# io-board-a-2.net
KiCad netlist of a schematic drawn in EAGLE
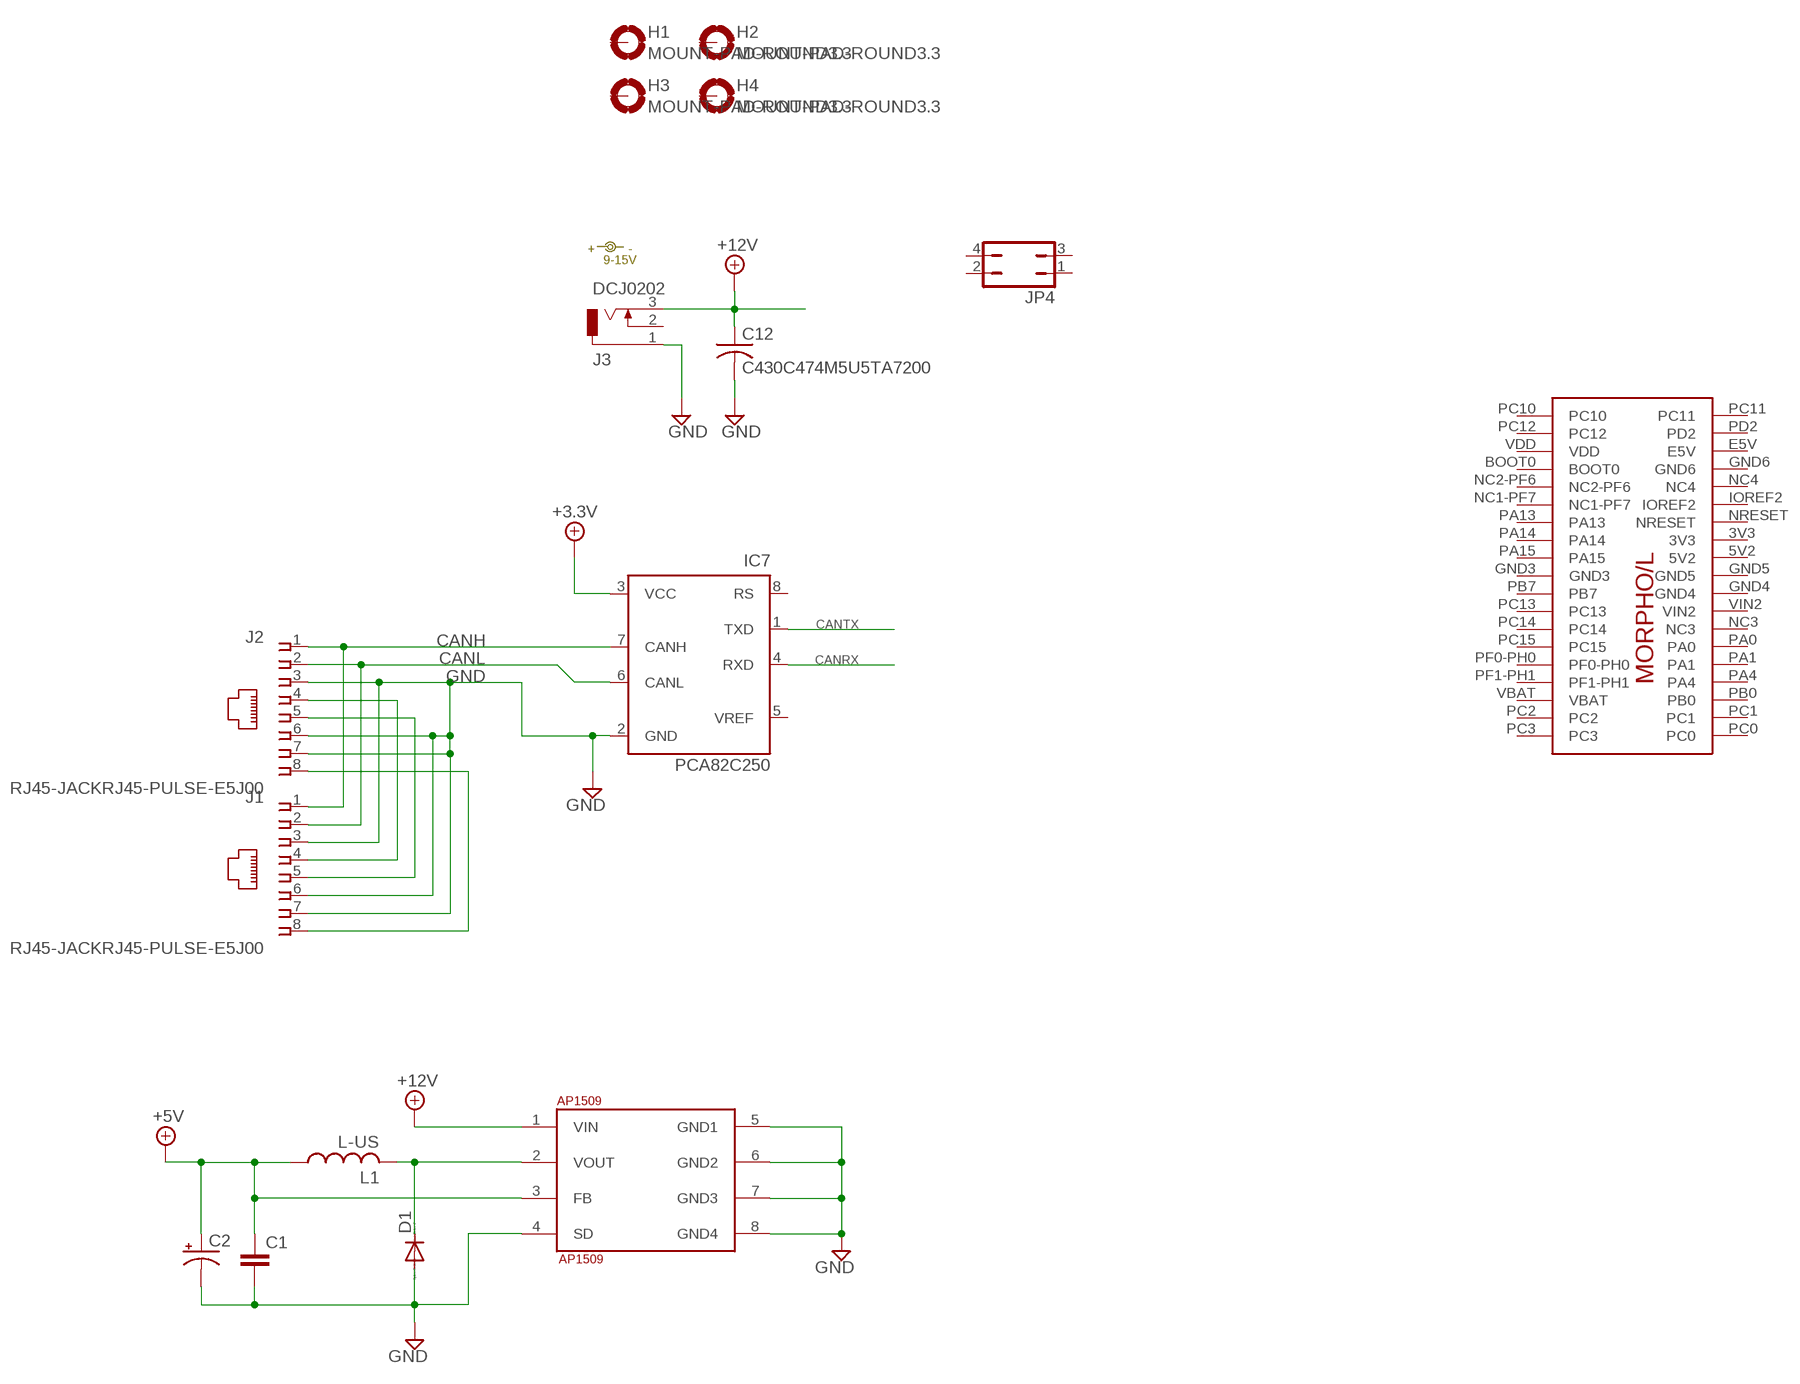
[diagram p0: schematic, sheet 1, part 1 of 2]
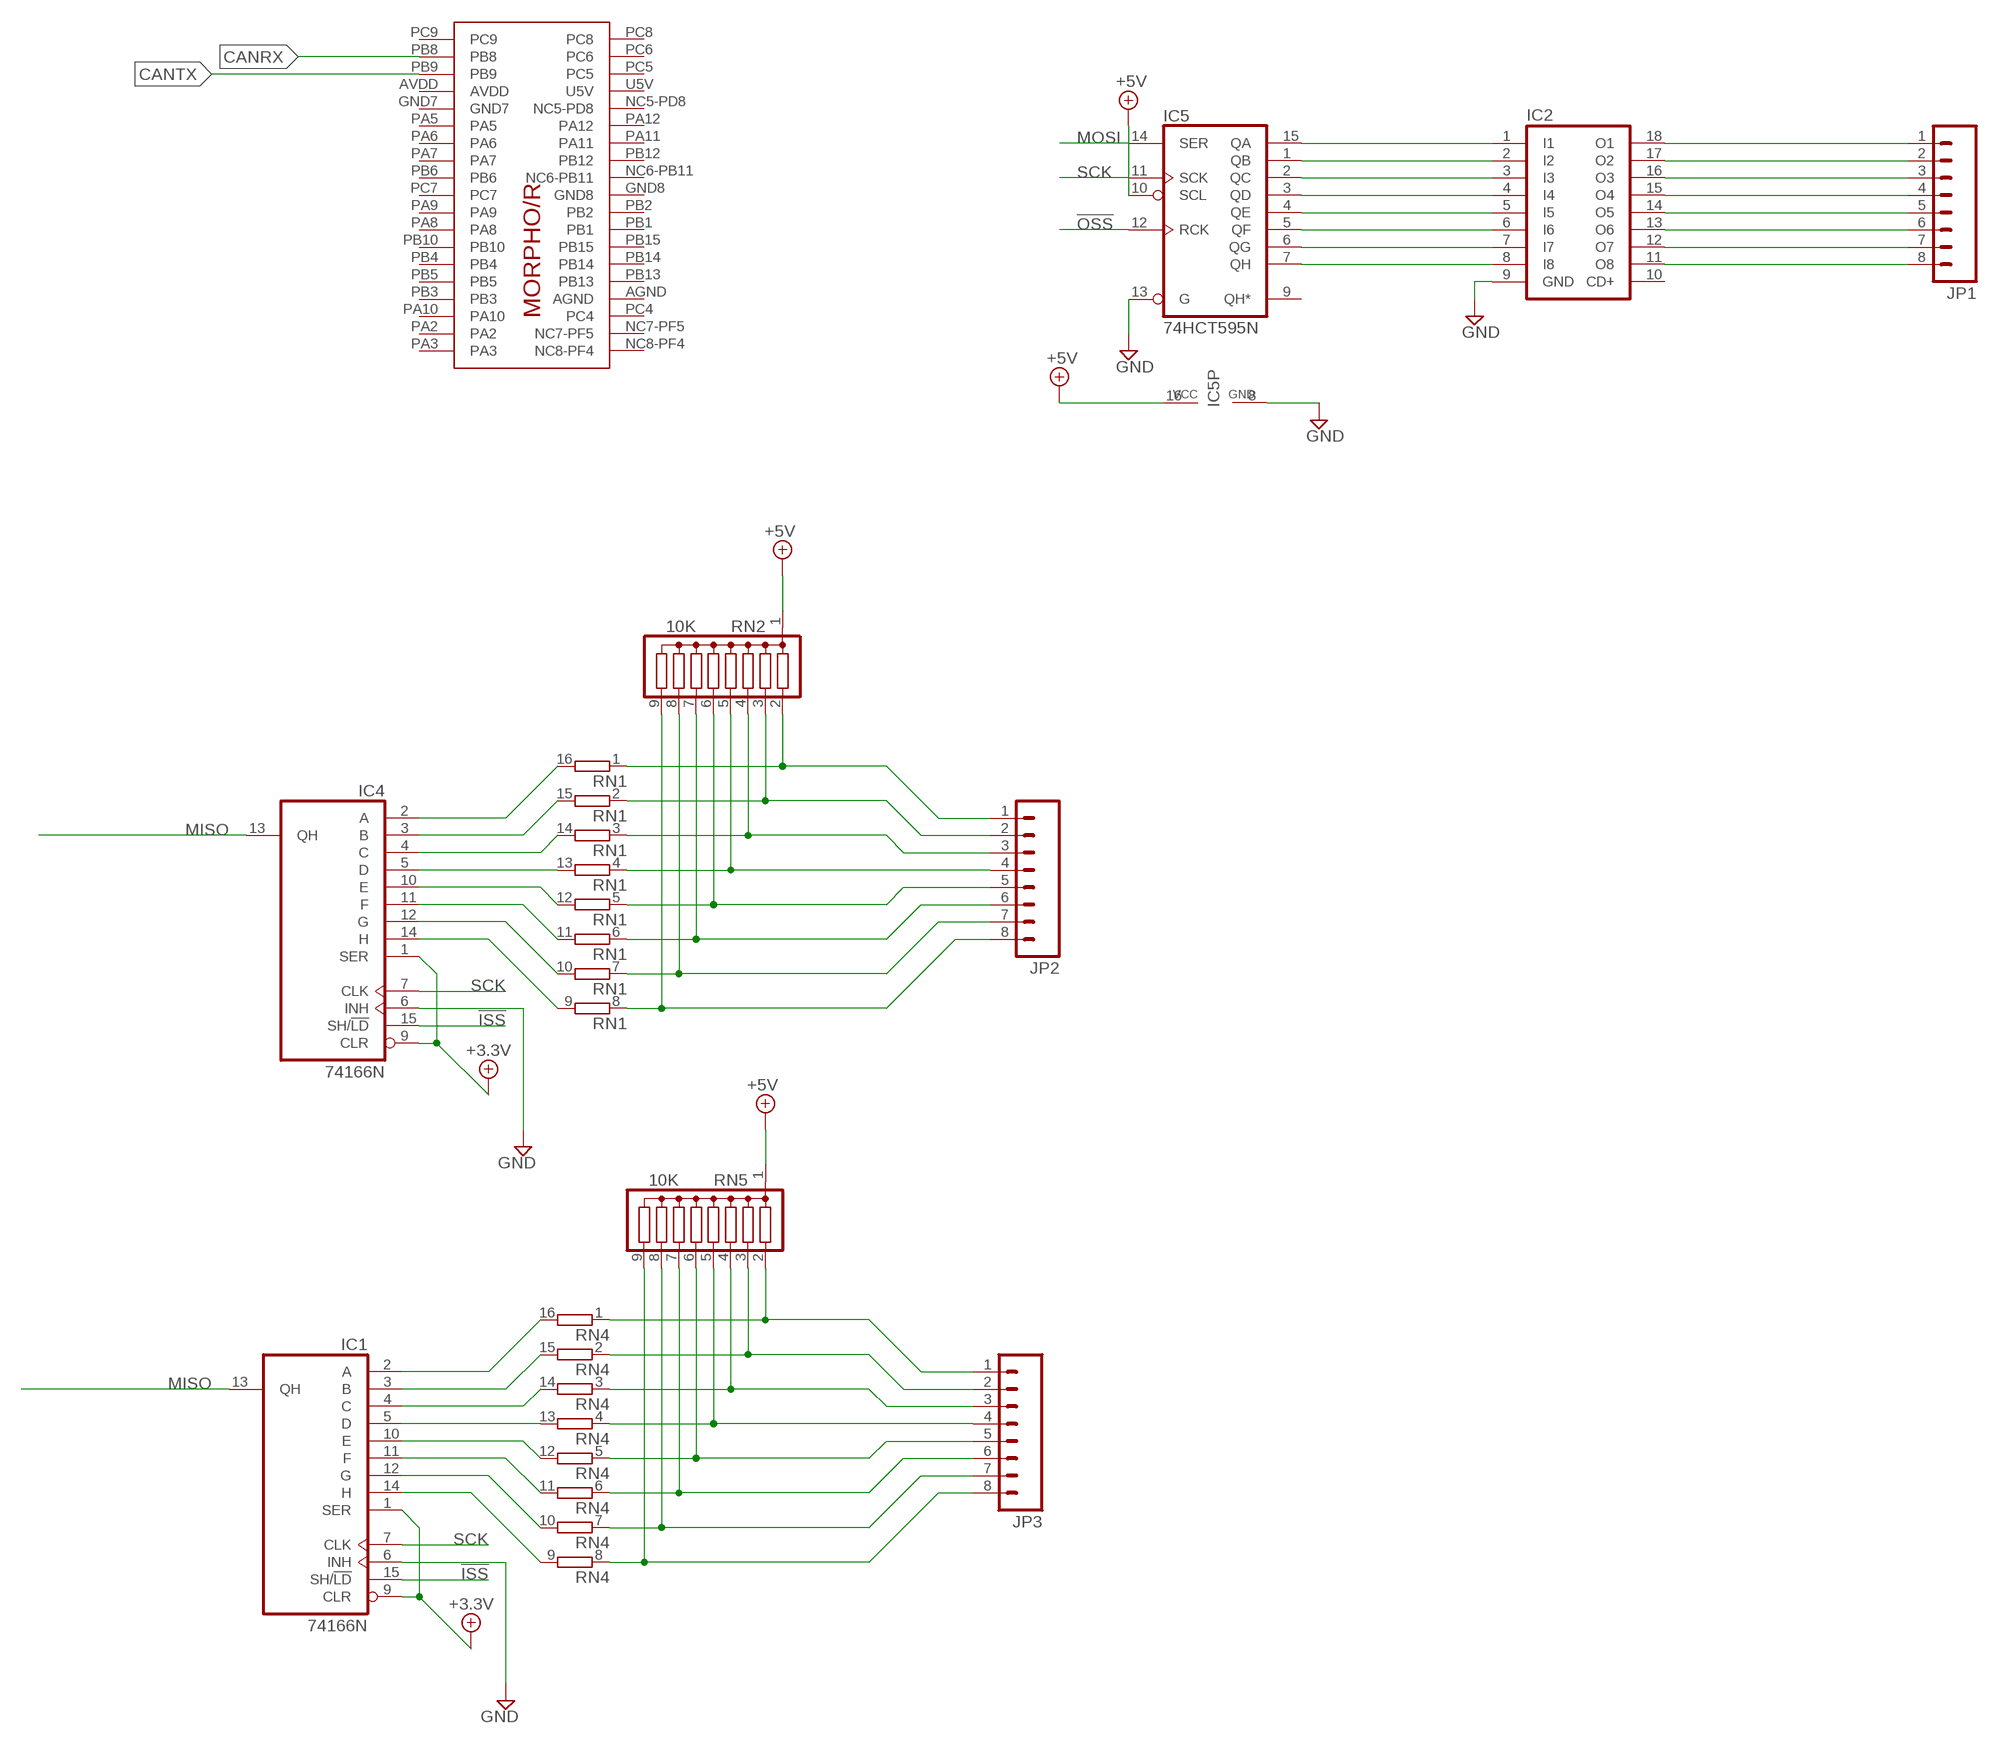
[diagram p1: schematic, sheet 1, part 2 of 2]

(export (version "E")
  (design (tool "Eeschema 10.0.6"))
  (components
    (comp (ref "+12V")
      (value "9-15V")
      (footprint "eagle-import:POWER_USAGE")
      (libsource (lib "eagle-import") (part "DOC-POWER_LABEL"))
    )
    (comp (ref "AP1509")
      (value "AP1509")
      (footprint "eagle-import:SO-08")
      (libsource (lib "eagle-import") (part "AP1509"))
    )
    (comp (ref "C1")
      (value "C-EUC1206")
      (footprint "eagle-import:C1206")
      (libsource (lib "eagle-import") (part "C-EUC1206"))
    )
    (comp (ref "C2")
      (value "CPOL-USE2.5-5")
      (footprint "eagle-import:E2,5-5")
      (libsource (lib "eagle-import") (part "CPOL-USE2.5-5"))
    )
    (comp (ref "C12")
      (value "C430C474M5U5TA7200")
      (footprint "eagle-import:C075-032X103")
      (libsource (lib "eagle-import") (part "C-US075-032X103"))
    )
    (comp (ref "D1")
      (value "DIODE-DO41-7.6")
      (footprint "eagle-import:DO41-7.6")
      (libsource (lib "eagle-import") (part "DIODE-DO41-7.6"))
    )
    (comp (ref "H1")
      (value "MOUNT-PAD-ROUND3.3")
      (footprint "eagle-import:3,3-PAD")
      (libsource (lib "eagle-import") (part "MOUNT-PAD-ROUND3.3"))
    )
    (comp (ref "H2")
      (value "MOUNT-PAD-ROUND3.3")
      (footprint "eagle-import:3,3-PAD")
      (libsource (lib "eagle-import") (part "MOUNT-PAD-ROUND3.3"))
    )
    (comp (ref "H3")
      (value "MOUNT-PAD-ROUND3.3")
      (footprint "eagle-import:3,3-PAD")
      (libsource (lib "eagle-import") (part "MOUNT-PAD-ROUND3.3"))
    )
    (comp (ref "H4")
      (value "MOUNT-PAD-ROUND3.3")
      (footprint "eagle-import:3,3-PAD")
      (libsource (lib "eagle-import") (part "MOUNT-PAD-ROUND3.3"))
    )
    (comp (ref "IC1")
      (value "74166N")
      (footprint "eagle-import:DIL16")
      (libsource (lib "eagle-import") (part "74166N"))
    )
    (comp (ref "IC2")
      (value "ULN2803A")
      (footprint "eagle-import:DIL18")
      (libsource (lib "eagle-import") (part "ULN2803A"))
    )
    (comp (ref "IC4")
      (value "74166N")
      (footprint "eagle-import:DIL16")
      (libsource (lib "eagle-import") (part "74166N"))
    )
    (comp (ref "IC5")
      (value "74HCT595N")
      (footprint "eagle-import:DIL16")
      (libsource (lib "eagle-import") (part "74595NHCT"))
    )
    (comp (ref "IC7")
      (value "PCA82C250")
      (footprint "eagle-import:DIL08")
      (libsource (lib "eagle-import") (part "PCA82C250"))
    )
    (comp (ref "J1")
      (value "RJ45-JACKRJ45-PULSE-E5J00")
      (footprint "eagle-import:RJ45-PULSE-E5J88")
      (libsource (lib "eagle-import") (part "RJ45-JACKRJ45-PULSE-E5J00"))
    )
    (comp (ref "J2")
      (value "RJ45-JACKRJ45-PULSE-E5J00")
      (footprint "eagle-import:RJ45-PULSE-E5J88")
      (libsource (lib "eagle-import") (part "RJ45-JACKRJ45-PULSE-E5J00"))
    )
    (comp (ref "J3")
      (value "DCJ0202")
      (footprint "eagle-import:DCJ0202")
      (libsource (lib "eagle-import") (part "DCJ0202"))
    )
    (comp (ref "JP1")
      (value "M08LOCK")
      (footprint "eagle-import:1X08_LOCK")
      (libsource (lib "eagle-import") (part "M08LOCK"))
    )
    (comp (ref "JP2")
      (value "M08LOCK")
      (footprint "eagle-import:1X08_LOCK")
      (libsource (lib "eagle-import") (part "M08LOCK"))
    )
    (comp (ref "JP3")
      (value "M08LOCK")
      (footprint "eagle-import:1X08_LOCK")
      (libsource (lib "eagle-import") (part "M08LOCK"))
    )
    (comp (ref "JP4")
      (value "JP2Q")
      (footprint "eagle-import:JP2Q")
      (libsource (lib "eagle-import") (part "JP2Q"))
    )
    (comp (ref "L1")
      (value "L-US")
      (footprint "eagle-import:L5-8,5")
      (libsource (lib "eagle-import") (part "L-US"))
    )
    (comp (ref "RN1")
      (value "8R-P")
      (footprint "eagle-import:DIL16")
      (libsource (lib "eagle-import") (part "8R-P"))
    )
    (comp (ref "RN2")
      (value "10K")
      (footprint "eagle-import:SIL9")
      (libsource (lib "eagle-import") (part "G08R"))
    )
    (comp (ref "RN4")
      (value "8R-P")
      (footprint "eagle-import:DIL16")
      (libsource (lib "eagle-import") (part "8R-P"))
    )
    (comp (ref "RN5")
      (value "10K")
      (footprint "eagle-import:SIL9")
      (libsource (lib "eagle-import") (part "G08R"))
    )
    (comp (ref "U$1")
      (value "NUCLEO_64_GENERIC")
      (footprint "eagle-import:NUCLEO_BRD_BASE64")
      (libsource (lib "eagle-import") (part "NUCLEO_64_GENERIC"))
    )
  )
  (nets
    (net (code "1") (name "+3.3V") (class "Default")
      (node (ref "IC1") (pin "1") (pinfunction "SER_1") (pintype "input"))
      (node (ref "IC1") (pin "9") (pinfunction "CLR_9") (pintype "input"))
      (node (ref "IC4") (pin "1") (pinfunction "SER_1") (pintype "input"))
      (node (ref "IC4") (pin "9") (pinfunction "CLR_9") (pintype "input"))
      (node (ref "IC7") (pin "3") (pinfunction "VCC_3") (pintype "power_in"))
    )
    (net (code "2") (name "+5V") (class "Default")
      (node (ref "AP1509") (pin "3") (pinfunction "FB_3") (pintype "bidirectional"))
      (node (ref "C1") (pin "1") (pinfunction "1_1") (pintype "passive"))
      (node (ref "C2") (pin "+") (pinfunction "+_+") (pintype "passive"))
      (node (ref "IC5") (pin "10") (pinfunction "SCL_10") (pintype "input"))
      (node (ref "IC5") (pin "16") (pinfunction "VCC_16") (pintype "power_in"))
      (node (ref "L1") (pin "1") (pinfunction "1_1") (pintype "passive"))
      (node (ref "RN2") (pin "1") (pinfunction "1_1") (pintype "passive"))
      (node (ref "RN5") (pin "1") (pinfunction "1_1") (pintype "passive"))
    )
    (net (code "3") (name "+12V") (class "Default")
      (node (ref "AP1509") (pin "1") (pinfunction "VIN_1") (pintype "bidirectional"))
      (node (ref "C12") (pin "1") (pinfunction "1_1") (pintype "passive"))
      (node (ref "J3") (pin "3") (pinfunction "3_3") (pintype "passive"))
    )
    (net (code "4") (name "/3V3") (class "Default")
      (node (ref "U$1") (pin "3V3") (pinfunction "3V3_3V3") (pintype "power_in"))
    )
    (net (code "5") (name "/5V2") (class "Default")
      (node (ref "U$1") (pin "5V2") (pinfunction "5V2_5V2") (pintype "power_in"))
    )
    (net (code "6") (name "/AGND") (class "Default")
      (node (ref "U$1") (pin "AGND") (pinfunction "AGND_AGND") (pintype "power_in"))
    )
    (net (code "7") (name "/AVDD") (class "Default")
      (node (ref "U$1") (pin "AVDD") (pinfunction "AVDD_AVDD") (pintype "power_in"))
    )
    (net (code "8") (name "/CANH") (class "Default")
      (node (ref "IC7") (pin "7") (pinfunction "CANH_7") (pintype "bidirectional"))
      (node (ref "J1") (pin "1") (pinfunction "1_1") (pintype "passive"))
      (node (ref "J2") (pin "1") (pinfunction "1_1") (pintype "passive"))
    )
    (net (code "9") (name "/CANL") (class "Default")
      (node (ref "IC7") (pin "6") (pinfunction "CANL_6") (pintype "bidirectional"))
      (node (ref "J1") (pin "2") (pinfunction "2_2") (pintype "passive"))
      (node (ref "J2") (pin "2") (pinfunction "2_2") (pintype "passive"))
    )
    (net (code "10") (name "/E5V") (class "Default")
      (node (ref "U$1") (pin "E5V") (pinfunction "E5V_E5V") (pintype "power_in"))
    )
    (net (code "11") (name "/GND3") (class "Default")
      (node (ref "U$1") (pin "GND3") (pinfunction "GND3_GND3") (pintype "power_in"))
    )
    (net (code "12") (name "/GND4") (class "Default")
      (node (ref "U$1") (pin "GND4") (pinfunction "GND4_GND4") (pintype "power_in"))
    )
    (net (code "13") (name "/GND5") (class "Default")
      (node (ref "U$1") (pin "GND5") (pinfunction "GND5_GND5") (pintype "power_in"))
    )
    (net (code "14") (name "/GND6") (class "Default")
      (node (ref "U$1") (pin "GND6") (pinfunction "GND6_GND6") (pintype "power_in"))
    )
    (net (code "15") (name "/GND7") (class "Default")
      (node (ref "U$1") (pin "GND7") (pinfunction "GND7_GND7") (pintype "power_in"))
    )
    (net (code "16") (name "/GND8") (class "Default")
      (node (ref "U$1") (pin "GND8") (pinfunction "GND8_GND8") (pintype "power_in"))
    )
    (net (code "17") (name "/MISO") (class "Default")
      (node (ref "IC1") (pin "13") (pinfunction "QH_13") (pintype "output"))
      (node (ref "IC4") (pin "13") (pinfunction "QH_13") (pintype "output"))
    )
    (net (code "18") (name "/MOSI") (class "Default")
      (node (ref "IC5") (pin "14") (pinfunction "SER_14") (pintype "input"))
    )
    (net (code "19") (name "/SCK") (class "Default")
      (node (ref "IC1") (pin "7") (pinfunction "CLK_7") (pintype "input"))
      (node (ref "IC4") (pin "7") (pinfunction "CLK_7") (pintype "input"))
      (node (ref "IC5") (pin "11") (pinfunction "SCK_11") (pintype "input"))
    )
    (net (code "20") (name "/U5V") (class "Default")
      (node (ref "U$1") (pin "U5V") (pinfunction "U5V_U5V") (pintype "power_in"))
    )
    (net (code "21") (name "/VBAT") (class "Default")
      (node (ref "U$1") (pin "VBAT") (pinfunction "VBAT_VBAT") (pintype "power_in"))
    )
    (net (code "22") (name "/VDD") (class "Default")
      (node (ref "U$1") (pin "VDD") (pinfunction "VDD_VDD") (pintype "power_in"))
    )
    (net (code "23") (name "/VIN2") (class "Default")
      (node (ref "U$1") (pin "VIN2") (pinfunction "VIN2_VIN2") (pintype "power_in"))
    )
    (net (code "24") (name "/~{ISS}") (class "Default")
      (node (ref "IC1") (pin "15") (pinfunction "SH/~{LD}_15") (pintype "input"))
      (node (ref "IC4") (pin "15") (pinfunction "SH/~{LD}_15") (pintype "input"))
    )
    (net (code "25") (name "/~{OSS}") (class "Default")
      (node (ref "IC5") (pin "12") (pinfunction "RCK_12") (pintype "input"))
    )
    (net (code "26") (name "CANRX") (class "Default")
      (node (ref "IC7") (pin "4") (pinfunction "RXD_4") (pintype "output"))
      (node (ref "U$1") (pin "PB8") (pinfunction "PB8_PB8") (pintype "bidirectional"))
    )
    (net (code "27") (name "CANTX") (class "Default")
      (node (ref "IC7") (pin "1") (pinfunction "TXD_1") (pintype "input"))
      (node (ref "U$1") (pin "PB9") (pinfunction "PB9_PB9") (pintype "bidirectional"))
    )
    (net (code "28") (name "GND") (class "Default")
      (node (ref "AP1509") (pin "4") (pinfunction "SD_4") (pintype "bidirectional"))
      (node (ref "AP1509") (pin "5") (pinfunction "GND1_5") (pintype "power_in"))
      (node (ref "AP1509") (pin "6") (pinfunction "GND2_6") (pintype "power_in"))
      (node (ref "AP1509") (pin "7") (pinfunction "GND3_7") (pintype "power_in"))
      (node (ref "AP1509") (pin "8") (pinfunction "GND4_8") (pintype "power_in"))
      (node (ref "C1") (pin "2") (pinfunction "2_2") (pintype "passive"))
      (node (ref "C12") (pin "2") (pinfunction "2_2") (pintype "passive"))
      (node (ref "C2") (pin "-") (pinfunction "-_-") (pintype "passive"))
      (node (ref "D1") (pin "A") (pinfunction "A_A") (pintype "passive"))
      (node (ref "IC1") (pin "6") (pinfunction "INH_6") (pintype "input"))
      (node (ref "IC2") (pin "9") (pinfunction "GND_9") (pintype "power_in"))
      (node (ref "IC4") (pin "6") (pinfunction "INH_6") (pintype "input"))
      (node (ref "IC5") (pin "13") (pinfunction "G_13") (pintype "input"))
      (node (ref "IC5") (pin "8") (pinfunction "GND_8") (pintype "power_in"))
      (node (ref "IC7") (pin "2") (pinfunction "GND_2") (pintype "power_in"))
      (node (ref "J1") (pin "3") (pinfunction "3_3") (pintype "passive"))
      (node (ref "J1") (pin "6") (pinfunction "6_6") (pintype "passive"))
      (node (ref "J1") (pin "7") (pinfunction "7_7") (pintype "passive"))
      (node (ref "J2") (pin "3") (pinfunction "3_3") (pintype "passive"))
      (node (ref "J2") (pin "6") (pinfunction "6_6") (pintype "passive"))
      (node (ref "J2") (pin "7") (pinfunction "7_7") (pintype "passive"))
      (node (ref "J3") (pin "1") (pinfunction "1_1") (pintype "passive"))
    )
    (net (code "29") (name "Net-(AP1509-VOUT)") (class "Default")
      (node (ref "AP1509") (pin "2") (pinfunction "VOUT_2") (pintype "bidirectional"))
      (node (ref "D1") (pin "C") (pinfunction "C_C") (pintype "passive"))
      (node (ref "L1") (pin "2") (pinfunction "2_2") (pintype "passive"))
    )
    (net (code "30") (name "Net-(IC1A-A)") (class "Default")
      (node (ref "IC1") (pin "2") (pinfunction "A_2") (pintype "input"))
      (node (ref "RN4") (pin "16") (pinfunction "2_16") (pintype "passive"))
    )
    (net (code "31") (name "Net-(IC1A-B)") (class "Default")
      (node (ref "IC1") (pin "3") (pinfunction "B_3") (pintype "input"))
      (node (ref "RN4") (pin "15") (pinfunction "2_15") (pintype "passive"))
    )
    (net (code "32") (name "Net-(IC1A-C)") (class "Default")
      (node (ref "IC1") (pin "4") (pinfunction "C_4") (pintype "input"))
      (node (ref "RN4") (pin "14") (pinfunction "2_14") (pintype "passive"))
    )
    (net (code "33") (name "Net-(IC1A-D)") (class "Default")
      (node (ref "IC1") (pin "5") (pinfunction "D_5") (pintype "input"))
      (node (ref "RN4") (pin "13") (pinfunction "2_13") (pintype "passive"))
    )
    (net (code "34") (name "Net-(IC1A-E)") (class "Default")
      (node (ref "IC1") (pin "10") (pinfunction "E_10") (pintype "input"))
      (node (ref "RN4") (pin "12") (pinfunction "2_12") (pintype "passive"))
    )
    (net (code "35") (name "Net-(IC1A-F)") (class "Default")
      (node (ref "IC1") (pin "11") (pinfunction "F_11") (pintype "input"))
      (node (ref "RN4") (pin "11") (pinfunction "2_11") (pintype "passive"))
    )
    (net (code "36") (name "Net-(IC1A-G)") (class "Default")
      (node (ref "IC1") (pin "12") (pinfunction "G_12") (pintype "input"))
      (node (ref "RN4") (pin "10") (pinfunction "2_10") (pintype "passive"))
    )
    (net (code "37") (name "Net-(IC1A-H)") (class "Default")
      (node (ref "IC1") (pin "14") (pinfunction "H_14") (pintype "input"))
      (node (ref "RN4") (pin "9") (pinfunction "2_9") (pintype "passive"))
    )
    (net (code "38") (name "Net-(IC2-I1)") (class "Default")
      (node (ref "IC2") (pin "1") (pinfunction "I1_1") (pintype "input"))
      (node (ref "IC5") (pin "15") (pinfunction "QA_15") (pintype "tri_state"))
    )
    (net (code "39") (name "Net-(IC2-I2)") (class "Default")
      (node (ref "IC2") (pin "2") (pinfunction "I2_2") (pintype "input"))
      (node (ref "IC5") (pin "1") (pinfunction "QB_1") (pintype "tri_state"))
    )
    (net (code "40") (name "Net-(IC2-I3)") (class "Default")
      (node (ref "IC2") (pin "3") (pinfunction "I3_3") (pintype "input"))
      (node (ref "IC5") (pin "2") (pinfunction "QC_2") (pintype "tri_state"))
    )
    (net (code "41") (name "Net-(IC2-I4)") (class "Default")
      (node (ref "IC2") (pin "4") (pinfunction "I4_4") (pintype "input"))
      (node (ref "IC5") (pin "3") (pinfunction "QD_3") (pintype "tri_state"))
    )
    (net (code "42") (name "Net-(IC2-I5)") (class "Default")
      (node (ref "IC2") (pin "5") (pinfunction "I5_5") (pintype "input"))
      (node (ref "IC5") (pin "4") (pinfunction "QE_4") (pintype "tri_state"))
    )
    (net (code "43") (name "Net-(IC2-I6)") (class "Default")
      (node (ref "IC2") (pin "6") (pinfunction "I6_6") (pintype "input"))
      (node (ref "IC5") (pin "5") (pinfunction "QF_5") (pintype "tri_state"))
    )
    (net (code "44") (name "Net-(IC2-I7)") (class "Default")
      (node (ref "IC2") (pin "7") (pinfunction "I7_7") (pintype "input"))
      (node (ref "IC5") (pin "6") (pinfunction "QG_6") (pintype "tri_state"))
    )
    (net (code "45") (name "Net-(IC2-I8)") (class "Default")
      (node (ref "IC2") (pin "8") (pinfunction "I8_8") (pintype "input"))
      (node (ref "IC5") (pin "7") (pinfunction "QH_7") (pintype "tri_state"))
    )
    (net (code "46") (name "Net-(IC2-O1)") (class "Default")
      (node (ref "IC2") (pin "18") (pinfunction "O1_18") (pintype "open_collector"))
      (node (ref "JP1") (pin "1") (pinfunction "1_1") (pintype "passive"))
    )
    (net (code "47") (name "Net-(IC2-O2)") (class "Default")
      (node (ref "IC2") (pin "17") (pinfunction "O2_17") (pintype "open_collector"))
      (node (ref "JP1") (pin "2") (pinfunction "2_2") (pintype "passive"))
    )
    (net (code "48") (name "Net-(IC2-O3)") (class "Default")
      (node (ref "IC2") (pin "16") (pinfunction "O3_16") (pintype "open_collector"))
      (node (ref "JP1") (pin "3") (pinfunction "3_3") (pintype "passive"))
    )
    (net (code "49") (name "Net-(IC2-O4)") (class "Default")
      (node (ref "IC2") (pin "15") (pinfunction "O4_15") (pintype "open_collector"))
      (node (ref "JP1") (pin "4") (pinfunction "4_4") (pintype "passive"))
    )
    (net (code "50") (name "Net-(IC2-O5)") (class "Default")
      (node (ref "IC2") (pin "14") (pinfunction "O5_14") (pintype "open_collector"))
      (node (ref "JP1") (pin "5") (pinfunction "5_5") (pintype "passive"))
    )
    (net (code "51") (name "Net-(IC2-O6)") (class "Default")
      (node (ref "IC2") (pin "13") (pinfunction "O6_13") (pintype "open_collector"))
      (node (ref "JP1") (pin "6") (pinfunction "6_6") (pintype "passive"))
    )
    (net (code "52") (name "Net-(IC2-O7)") (class "Default")
      (node (ref "IC2") (pin "12") (pinfunction "O7_12") (pintype "open_collector"))
      (node (ref "JP1") (pin "7") (pinfunction "7_7") (pintype "passive"))
    )
    (net (code "53") (name "Net-(IC2-O8)") (class "Default")
      (node (ref "IC2") (pin "11") (pinfunction "O8_11") (pintype "open_collector"))
      (node (ref "JP1") (pin "8") (pinfunction "8_8") (pintype "passive"))
    )
    (net (code "54") (name "Net-(IC4A-A)") (class "Default")
      (node (ref "IC4") (pin "2") (pinfunction "A_2") (pintype "input"))
      (node (ref "RN1") (pin "16") (pinfunction "2_16") (pintype "passive"))
    )
    (net (code "55") (name "Net-(IC4A-B)") (class "Default")
      (node (ref "IC4") (pin "3") (pinfunction "B_3") (pintype "input"))
      (node (ref "RN1") (pin "15") (pinfunction "2_15") (pintype "passive"))
    )
    (net (code "56") (name "Net-(IC4A-C)") (class "Default")
      (node (ref "IC4") (pin "4") (pinfunction "C_4") (pintype "input"))
      (node (ref "RN1") (pin "14") (pinfunction "2_14") (pintype "passive"))
    )
    (net (code "57") (name "Net-(IC4A-D)") (class "Default")
      (node (ref "IC4") (pin "5") (pinfunction "D_5") (pintype "input"))
      (node (ref "RN1") (pin "13") (pinfunction "2_13") (pintype "passive"))
    )
    (net (code "58") (name "Net-(IC4A-E)") (class "Default")
      (node (ref "IC4") (pin "10") (pinfunction "E_10") (pintype "input"))
      (node (ref "RN1") (pin "12") (pinfunction "2_12") (pintype "passive"))
    )
    (net (code "59") (name "Net-(IC4A-F)") (class "Default")
      (node (ref "IC4") (pin "11") (pinfunction "F_11") (pintype "input"))
      (node (ref "RN1") (pin "11") (pinfunction "2_11") (pintype "passive"))
    )
    (net (code "60") (name "Net-(IC4A-G)") (class "Default")
      (node (ref "IC4") (pin "12") (pinfunction "G_12") (pintype "input"))
      (node (ref "RN1") (pin "10") (pinfunction "2_10") (pintype "passive"))
    )
    (net (code "61") (name "Net-(IC4A-H)") (class "Default")
      (node (ref "IC4") (pin "14") (pinfunction "H_14") (pintype "input"))
      (node (ref "RN1") (pin "9") (pinfunction "2_9") (pintype "passive"))
    )
    (net (code "62") (name "Net-(J1-Pad4)") (class "Default")
      (node (ref "J1") (pin "4") (pinfunction "4_4") (pintype "passive"))
      (node (ref "J2") (pin "4") (pinfunction "4_4") (pintype "passive"))
    )
    (net (code "63") (name "Net-(J1-Pad5)") (class "Default")
      (node (ref "J1") (pin "5") (pinfunction "5_5") (pintype "passive"))
      (node (ref "J2") (pin "5") (pinfunction "5_5") (pintype "passive"))
    )
    (net (code "64") (name "Net-(J1-Pad8)") (class "Default")
      (node (ref "J1") (pin "8") (pinfunction "8_8") (pintype "passive"))
      (node (ref "J2") (pin "8") (pinfunction "8_8") (pintype "passive"))
    )
    (net (code "65") (name "Net-(JP2-Pad1)") (class "Default")
      (node (ref "JP2") (pin "1") (pinfunction "1_1") (pintype "passive"))
      (node (ref "RN1") (pin "1") (pinfunction "1_1") (pintype "passive"))
      (node (ref "RN2") (pin "2") (pinfunction "2_2") (pintype "passive"))
    )
    (net (code "66") (name "Net-(JP3-Pad1)") (class "Default")
      (node (ref "JP3") (pin "1") (pinfunction "1_1") (pintype "passive"))
      (node (ref "RN4") (pin "1") (pinfunction "1_1") (pintype "passive"))
      (node (ref "RN5") (pin "2") (pinfunction "2_2") (pintype "passive"))
    )
    (net (code "67") (name "Net-(RN1B-1)") (class "Default")
      (node (ref "JP2") (pin "2") (pinfunction "2_2") (pintype "passive"))
      (node (ref "RN1") (pin "2") (pinfunction "1_2") (pintype "passive"))
      (node (ref "RN2") (pin "3") (pinfunction "3_3") (pintype "passive"))
    )
    (net (code "68") (name "Net-(RN1C-1)") (class "Default")
      (node (ref "JP2") (pin "3") (pinfunction "3_3") (pintype "passive"))
      (node (ref "RN1") (pin "3") (pinfunction "1_3") (pintype "passive"))
      (node (ref "RN2") (pin "4") (pinfunction "4_4") (pintype "passive"))
    )
    (net (code "69") (name "Net-(RN1D-1)") (class "Default")
      (node (ref "JP2") (pin "4") (pinfunction "4_4") (pintype "passive"))
      (node (ref "RN1") (pin "4") (pinfunction "1_4") (pintype "passive"))
      (node (ref "RN2") (pin "5") (pinfunction "5_5") (pintype "passive"))
    )
    (net (code "70") (name "Net-(RN1E-1)") (class "Default")
      (node (ref "JP2") (pin "5") (pinfunction "5_5") (pintype "passive"))
      (node (ref "RN1") (pin "5") (pinfunction "1_5") (pintype "passive"))
      (node (ref "RN2") (pin "6") (pinfunction "6_6") (pintype "passive"))
    )
    (net (code "71") (name "Net-(RN1F-1)") (class "Default")
      (node (ref "JP2") (pin "6") (pinfunction "6_6") (pintype "passive"))
      (node (ref "RN1") (pin "6") (pinfunction "1_6") (pintype "passive"))
      (node (ref "RN2") (pin "7") (pinfunction "7_7") (pintype "passive"))
    )
    (net (code "72") (name "Net-(RN1G-1)") (class "Default")
      (node (ref "JP2") (pin "7") (pinfunction "7_7") (pintype "passive"))
      (node (ref "RN1") (pin "7") (pinfunction "1_7") (pintype "passive"))
      (node (ref "RN2") (pin "8") (pinfunction "8_8") (pintype "passive"))
    )
    (net (code "73") (name "Net-(RN1H-1)") (class "Default")
      (node (ref "JP2") (pin "8") (pinfunction "8_8") (pintype "passive"))
      (node (ref "RN1") (pin "8") (pinfunction "1_8") (pintype "passive"))
      (node (ref "RN2") (pin "9") (pinfunction "9_9") (pintype "passive"))
    )
    (net (code "74") (name "Net-(RN4B-1)") (class "Default")
      (node (ref "JP3") (pin "2") (pinfunction "2_2") (pintype "passive"))
      (node (ref "RN4") (pin "2") (pinfunction "1_2") (pintype "passive"))
      (node (ref "RN5") (pin "3") (pinfunction "3_3") (pintype "passive"))
    )
    (net (code "75") (name "Net-(RN4C-1)") (class "Default")
      (node (ref "JP3") (pin "3") (pinfunction "3_3") (pintype "passive"))
      (node (ref "RN4") (pin "3") (pinfunction "1_3") (pintype "passive"))
      (node (ref "RN5") (pin "4") (pinfunction "4_4") (pintype "passive"))
    )
    (net (code "76") (name "Net-(RN4D-1)") (class "Default")
      (node (ref "JP3") (pin "4") (pinfunction "4_4") (pintype "passive"))
      (node (ref "RN4") (pin "4") (pinfunction "1_4") (pintype "passive"))
      (node (ref "RN5") (pin "5") (pinfunction "5_5") (pintype "passive"))
    )
    (net (code "77") (name "Net-(RN4E-1)") (class "Default")
      (node (ref "JP3") (pin "5") (pinfunction "5_5") (pintype "passive"))
      (node (ref "RN4") (pin "5") (pinfunction "1_5") (pintype "passive"))
      (node (ref "RN5") (pin "6") (pinfunction "6_6") (pintype "passive"))
    )
    (net (code "78") (name "Net-(RN4F-1)") (class "Default")
      (node (ref "JP3") (pin "6") (pinfunction "6_6") (pintype "passive"))
      (node (ref "RN4") (pin "6") (pinfunction "1_6") (pintype "passive"))
      (node (ref "RN5") (pin "7") (pinfunction "7_7") (pintype "passive"))
    )
    (net (code "79") (name "Net-(RN4G-1)") (class "Default")
      (node (ref "JP3") (pin "7") (pinfunction "7_7") (pintype "passive"))
      (node (ref "RN4") (pin "7") (pinfunction "1_7") (pintype "passive"))
      (node (ref "RN5") (pin "8") (pinfunction "8_8") (pintype "passive"))
    )
    (net (code "80") (name "Net-(RN4H-1)") (class "Default")
      (node (ref "JP3") (pin "8") (pinfunction "8_8") (pintype "passive"))
      (node (ref "RN4") (pin "8") (pinfunction "1_8") (pintype "passive"))
      (node (ref "RN5") (pin "9") (pinfunction "9_9") (pintype "passive"))
    )
    (net (code "81") (name "unconnected-(H1-MOUNT-PadB3,3)") (class "Default")
      (node (ref "H1") (pin "B3,3") (pinfunction "MOUNT_B3,3") (pintype "passive"))
    )
    (net (code "82") (name "unconnected-(H2-MOUNT-PadB3,3)") (class "Default")
      (node (ref "H2") (pin "B3,3") (pinfunction "MOUNT_B3,3") (pintype "passive"))
    )
    (net (code "83") (name "unconnected-(H3-MOUNT-PadB3,3)") (class "Default")
      (node (ref "H3") (pin "B3,3") (pinfunction "MOUNT_B3,3") (pintype "passive"))
    )
    (net (code "84") (name "unconnected-(H4-MOUNT-PadB3,3)") (class "Default")
      (node (ref "H4") (pin "B3,3") (pinfunction "MOUNT_B3,3") (pintype "passive"))
    )
    (net (code "85") (name "unconnected-(IC2-CD+-Pad10)") (class "Default")
      (node (ref "IC2") (pin "10") (pinfunction "CD+_10") (pintype "passive"))
    )
    (net (code "86") (name "unconnected-(IC5A-QH*-Pad9)") (class "Default")
      (node (ref "IC5") (pin "9") (pinfunction "QH*_9") (pintype "tri_state"))
    )
    (net (code "87") (name "unconnected-(IC7-RS-Pad8)") (class "Default")
      (node (ref "IC7") (pin "8") (pinfunction "RS_8") (pintype "input"))
    )
    (net (code "88") (name "unconnected-(IC7-VREF-Pad5)") (class "Default")
      (node (ref "IC7") (pin "5") (pinfunction "VREF_5") (pintype "output"))
    )
    (net (code "89") (name "unconnected-(J3-Pad2)") (class "Default")
      (node (ref "J3") (pin "2") (pinfunction "2_2") (pintype "passive"))
    )
    (net (code "90") (name "unconnected-(JP4-Pad1)") (class "Default")
      (node (ref "JP4") (pin "1") (pinfunction "1_1") (pintype "passive"))
    )
    (net (code "91") (name "unconnected-(JP4-Pad2)") (class "Default")
      (node (ref "JP4") (pin "2") (pinfunction "2_2") (pintype "passive"))
    )
    (net (code "92") (name "unconnected-(JP4-Pad3)") (class "Default")
      (node (ref "JP4") (pin "3") (pinfunction "3_3") (pintype "passive"))
    )
    (net (code "93") (name "unconnected-(JP4-Pad4)") (class "Default")
      (node (ref "JP4") (pin "4") (pinfunction "4_4") (pintype "passive"))
    )
    (net (code "94") (name "unconnected-(U$1-PadBOOT0)") (class "Default")
      (node (ref "U$1") (pin "BOOT0") (pinfunction "BOOT0_BOOT0") (pintype "bidirectional"))
    )
    (net (code "95") (name "unconnected-(U$1-PadIOREF2)") (class "Default")
      (node (ref "U$1") (pin "IOREF2") (pinfunction "IOREF2_IOREF2") (pintype "input"))
    )
    (net (code "96") (name "unconnected-(U$1-PadNC1-PF7)") (class "Default")
      (node (ref "U$1") (pin "NC1-PF7") (pinfunction "NC1-PF7_NC1-PF7") (pintype "bidirectional"))
    )
    (net (code "97") (name "unconnected-(U$1-PadNC2-PF6)") (class "Default")
      (node (ref "U$1") (pin "NC2-PF6") (pinfunction "NC2-PF6_NC2-PF6") (pintype "bidirectional"))
    )
    (net (code "98") (name "unconnected-(U$1-PadNC3)") (class "Default")
      (node (ref "U$1") (pin "NC3") (pinfunction "NC3_NC3") (pintype "no_connect"))
    )
    (net (code "99") (name "unconnected-(U$1-PadNC4)") (class "Default")
      (node (ref "U$1") (pin "NC4") (pinfunction "NC4_NC4") (pintype "no_connect"))
    )
    (net (code "100") (name "unconnected-(U$1-PadNC5-PD8)") (class "Default")
      (node (ref "U$1") (pin "NC5-PD8") (pinfunction "NC5-PD8_NC5-PD8") (pintype "bidirectional"))
    )
    (net (code "101") (name "unconnected-(U$1-PadNC6-PB11)") (class "Default")
      (node (ref "U$1") (pin "NC6-PB11") (pinfunction "NC6-PB11_NC6-PB11") (pintype "no_connect"))
    )
    (net (code "102") (name "unconnected-(U$1-PadNC7-PF5)") (class "Default")
      (node (ref "U$1") (pin "NC7-PF5") (pinfunction "NC7-PF5_NC7-PF5") (pintype "bidirectional"))
    )
    (net (code "103") (name "unconnected-(U$1-PadNC8-PF4)") (class "Default")
      (node (ref "U$1") (pin "NC8-PF4") (pinfunction "NC8-PF4_NC8-PF4") (pintype "bidirectional"))
    )
    (net (code "104") (name "unconnected-(U$1-PadNRESET)") (class "Default")
      (node (ref "U$1") (pin "NRESET") (pinfunction "NRESET_NRESET") (pintype "input"))
    )
    (net (code "105") (name "unconnected-(U$1-PadPA0)") (class "Default")
      (node (ref "U$1") (pin "PA0") (pinfunction "PA0_PA0") (pintype "bidirectional"))
    )
    (net (code "106") (name "unconnected-(U$1-PadPA1)") (class "Default")
      (node (ref "U$1") (pin "PA1") (pinfunction "PA1_PA1") (pintype "bidirectional"))
    )
    (net (code "107") (name "unconnected-(U$1-PadPA2)") (class "Default")
      (node (ref "U$1") (pin "PA2") (pinfunction "PA2_PA2") (pintype "bidirectional"))
    )
    (net (code "108") (name "unconnected-(U$1-PadPA3)") (class "Default")
      (node (ref "U$1") (pin "PA3") (pinfunction "PA3_PA3") (pintype "bidirectional"))
    )
    (net (code "109") (name "unconnected-(U$1-PadPA4)") (class "Default")
      (node (ref "U$1") (pin "PA4") (pinfunction "PA4_PA4") (pintype "bidirectional"))
    )
    (net (code "110") (name "unconnected-(U$1-PadPA5)") (class "Default")
      (node (ref "U$1") (pin "PA5") (pinfunction "PA5_PA5") (pintype "bidirectional"))
    )
    (net (code "111") (name "unconnected-(U$1-PadPA6)") (class "Default")
      (node (ref "U$1") (pin "PA6") (pinfunction "PA6_PA6") (pintype "bidirectional"))
    )
    (net (code "112") (name "unconnected-(U$1-PadPA7)") (class "Default")
      (node (ref "U$1") (pin "PA7") (pinfunction "PA7_PA7") (pintype "bidirectional"))
    )
    (net (code "113") (name "unconnected-(U$1-PadPA8)") (class "Default")
      (node (ref "U$1") (pin "PA8") (pinfunction "PA8_PA8") (pintype "bidirectional"))
    )
    (net (code "114") (name "unconnected-(U$1-PadPA9)") (class "Default")
      (node (ref "U$1") (pin "PA9") (pinfunction "PA9_PA9") (pintype "bidirectional"))
    )
    (net (code "115") (name "unconnected-(U$1-PadPA10)") (class "Default")
      (node (ref "U$1") (pin "PA10") (pinfunction "PA10_PA10") (pintype "bidirectional"))
    )
    (net (code "116") (name "unconnected-(U$1-PadPA11)") (class "Default")
      (node (ref "U$1") (pin "PA11") (pinfunction "PA11_PA11") (pintype "bidirectional"))
    )
    (net (code "117") (name "unconnected-(U$1-PadPA12)") (class "Default")
      (node (ref "U$1") (pin "PA12") (pinfunction "PA12_PA12") (pintype "bidirectional"))
    )
    (net (code "118") (name "unconnected-(U$1-PadPA13)") (class "Default")
      (node (ref "U$1") (pin "PA13") (pinfunction "PA13_PA13") (pintype "bidirectional"))
    )
    (net (code "119") (name "unconnected-(U$1-PadPA14)") (class "Default")
      (node (ref "U$1") (pin "PA14") (pinfunction "PA14_PA14") (pintype "bidirectional"))
    )
    (net (code "120") (name "unconnected-(U$1-PadPA15)") (class "Default")
      (node (ref "U$1") (pin "PA15") (pinfunction "PA15_PA15") (pintype "bidirectional"))
    )
    (net (code "121") (name "unconnected-(U$1-PadPB0)") (class "Default")
      (node (ref "U$1") (pin "PB0") (pinfunction "PB0_PB0") (pintype "bidirectional"))
    )
    (net (code "122") (name "unconnected-(U$1-PadPB1)") (class "Default")
      (node (ref "U$1") (pin "PB1") (pinfunction "PB1_PB1") (pintype "bidirectional"))
    )
    (net (code "123") (name "unconnected-(U$1-PadPB2)") (class "Default")
      (node (ref "U$1") (pin "PB2") (pinfunction "PB2_PB2") (pintype "bidirectional"))
    )
    (net (code "124") (name "unconnected-(U$1-PadPB3)") (class "Default")
      (node (ref "U$1") (pin "PB3") (pinfunction "PB3_PB3") (pintype "bidirectional"))
    )
    (net (code "125") (name "unconnected-(U$1-PadPB4)") (class "Default")
      (node (ref "U$1") (pin "PB4") (pinfunction "PB4_PB4") (pintype "bidirectional"))
    )
    (net (code "126") (name "unconnected-(U$1-PadPB5)") (class "Default")
      (node (ref "U$1") (pin "PB5") (pinfunction "PB5_PB5") (pintype "bidirectional"))
    )
    (net (code "127") (name "unconnected-(U$1-PadPB6)") (class "Default")
      (node (ref "U$1") (pin "PB6") (pinfunction "PB6_PB6") (pintype "bidirectional"))
    )
    (net (code "128") (name "unconnected-(U$1-PadPB7)") (class "Default")
      (node (ref "U$1") (pin "PB7") (pinfunction "PB7_PB7") (pintype "bidirectional"))
    )
    (net (code "129") (name "unconnected-(U$1-PadPB10)") (class "Default")
      (node (ref "U$1") (pin "PB10") (pinfunction "PB10_PB10") (pintype "bidirectional"))
    )
    (net (code "130") (name "unconnected-(U$1-PadPB12)") (class "Default")
      (node (ref "U$1") (pin "PB12") (pinfunction "PB12_PB12") (pintype "bidirectional"))
    )
    (net (code "131") (name "unconnected-(U$1-PadPB13)") (class "Default")
      (node (ref "U$1") (pin "PB13") (pinfunction "PB13_PB13") (pintype "bidirectional"))
    )
    (net (code "132") (name "unconnected-(U$1-PadPB14)") (class "Default")
      (node (ref "U$1") (pin "PB14") (pinfunction "PB14_PB14") (pintype "bidirectional"))
    )
    (net (code "133") (name "unconnected-(U$1-PadPB15)") (class "Default")
      (node (ref "U$1") (pin "PB15") (pinfunction "PB15_PB15") (pintype "bidirectional"))
    )
    (net (code "134") (name "unconnected-(U$1-PadPC0)") (class "Default")
      (node (ref "U$1") (pin "PC0") (pinfunction "PC0_PC0") (pintype "bidirectional"))
    )
    (net (code "135") (name "unconnected-(U$1-PadPC1)") (class "Default")
      (node (ref "U$1") (pin "PC1") (pinfunction "PC1_PC1") (pintype "bidirectional"))
    )
    (net (code "136") (name "unconnected-(U$1-PadPC2)") (class "Default")
      (node (ref "U$1") (pin "PC2") (pinfunction "PC2_PC2") (pintype "bidirectional"))
    )
    (net (code "137") (name "unconnected-(U$1-PadPC3)") (class "Default")
      (node (ref "U$1") (pin "PC3") (pinfunction "PC3_PC3") (pintype "bidirectional"))
    )
    (net (code "138") (name "unconnected-(U$1-PadPC4)") (class "Default")
      (node (ref "U$1") (pin "PC4") (pinfunction "PC4_PC4") (pintype "bidirectional"))
    )
    (net (code "139") (name "unconnected-(U$1-PadPC5)") (class "Default")
      (node (ref "U$1") (pin "PC5") (pinfunction "PC5_PC5") (pintype "bidirectional"))
    )
    (net (code "140") (name "unconnected-(U$1-PadPC6)") (class "Default")
      (node (ref "U$1") (pin "PC6") (pinfunction "PC6_PC6") (pintype "bidirectional"))
    )
    (net (code "141") (name "unconnected-(U$1-PadPC7)") (class "Default")
      (node (ref "U$1") (pin "PC7") (pinfunction "PC7_PC7") (pintype "bidirectional"))
    )
    (net (code "142") (name "unconnected-(U$1-PadPC8)") (class "Default")
      (node (ref "U$1") (pin "PC8") (pinfunction "PC8_PC8") (pintype "bidirectional"))
    )
    (net (code "143") (name "unconnected-(U$1-PadPC9)") (class "Default")
      (node (ref "U$1") (pin "PC9") (pinfunction "PC9_PC9") (pintype "bidirectional"))
    )
    (net (code "144") (name "unconnected-(U$1-PadPC10)") (class "Default")
      (node (ref "U$1") (pin "PC10") (pinfunction "PC10_PC10") (pintype "bidirectional"))
    )
    (net (code "145") (name "unconnected-(U$1-PadPC11)") (class "Default")
      (node (ref "U$1") (pin "PC11") (pinfunction "PC11_PC11") (pintype "bidirectional"))
    )
    (net (code "146") (name "unconnected-(U$1-PadPC12)") (class "Default")
      (node (ref "U$1") (pin "PC12") (pinfunction "PC12_PC12") (pintype "bidirectional"))
    )
    (net (code "147") (name "unconnected-(U$1-PadPC13)") (class "Default")
      (node (ref "U$1") (pin "PC13") (pinfunction "PC13_PC13") (pintype "bidirectional"))
    )
    (net (code "148") (name "unconnected-(U$1-PadPC14)") (class "Default")
      (node (ref "U$1") (pin "PC14") (pinfunction "PC14_PC14") (pintype "bidirectional"))
    )
    (net (code "149") (name "unconnected-(U$1-PadPC15)") (class "Default")
      (node (ref "U$1") (pin "PC15") (pinfunction "PC15_PC15") (pintype "bidirectional"))
    )
    (net (code "150") (name "unconnected-(U$1-PadPD2)") (class "Default")
      (node (ref "U$1") (pin "PD2") (pinfunction "PD2_PD2") (pintype "bidirectional"))
    )
    (net (code "151") (name "unconnected-(U$1-PadPF0-PH0)") (class "Default")
      (node (ref "U$1") (pin "PF0-PH0") (pinfunction "PF0-PH0_PF0-PH0") (pintype "bidirectional"))
    )
    (net (code "152") (name "unconnected-(U$1-PadPF1-PH1)") (class "Default")
      (node (ref "U$1") (pin "PF1-PH1") (pinfunction "PF1-PH1_PF1-PH1") (pintype "bidirectional"))
    )
  )
)
